# power_regulator_wii.net
KiCad netlist of a schematic drawn in EAGLE
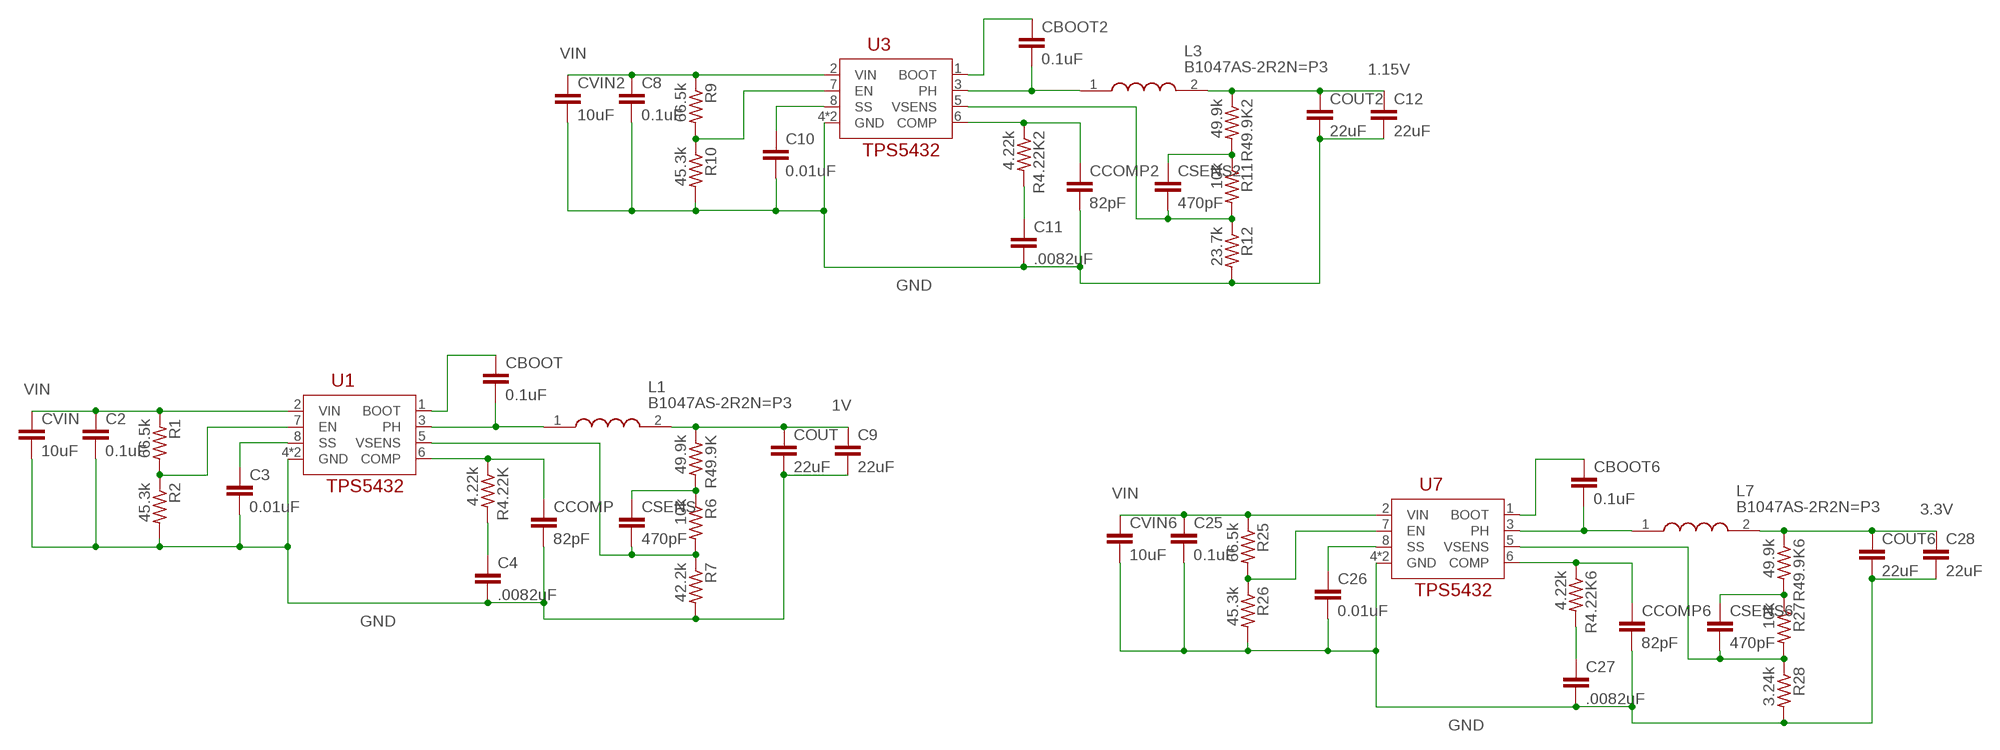
[diagram p0: schematic, sheet 1]

(export (version "E")
  (design (tool "Eeschema 10.0.6"))
  (components
    (comp (ref "C2")
      (value "0.1uF")
      (footprint "eagle-import:C0603")
      (libsource (lib "eagle-import") (part "C-EUC0603"))
    )
    (comp (ref "C3")
      (value "0.01uF")
      (footprint "eagle-import:C0603")
      (libsource (lib "eagle-import") (part "C-EUC0603"))
    )
    (comp (ref "C4")
      (value ".0082uF")
      (footprint "eagle-import:C0603")
      (libsource (lib "eagle-import") (part "C-EUC0603"))
    )
    (comp (ref "C8")
      (value "0.1uF")
      (footprint "eagle-import:C0603")
      (libsource (lib "eagle-import") (part "C-EUC0603"))
    )
    (comp (ref "C9")
      (value "22uF")
      (footprint "eagle-import:C0603")
      (libsource (lib "eagle-import") (part "C-EUC0603"))
    )
    (comp (ref "C10")
      (value "0.01uF")
      (footprint "eagle-import:C0603")
      (libsource (lib "eagle-import") (part "C-EUC0603"))
    )
    (comp (ref "C11")
      (value ".0082uF")
      (footprint "eagle-import:C0603")
      (libsource (lib "eagle-import") (part "C-EUC0603"))
    )
    (comp (ref "C12")
      (value "22uF")
      (footprint "eagle-import:C0603")
      (libsource (lib "eagle-import") (part "C-EUC0603"))
    )
    (comp (ref "C25")
      (value "0.1uF")
      (footprint "eagle-import:C0603")
      (libsource (lib "eagle-import") (part "C-EUC0603"))
    )
    (comp (ref "C26")
      (value "0.01uF")
      (footprint "eagle-import:C0603")
      (libsource (lib "eagle-import") (part "C-EUC0603"))
    )
    (comp (ref "C27")
      (value ".0082uF")
      (footprint "eagle-import:C0603")
      (libsource (lib "eagle-import") (part "C-EUC0603"))
    )
    (comp (ref "C28")
      (value "22uF")
      (footprint "eagle-import:C0603")
      (libsource (lib "eagle-import") (part "C-EUC0603"))
    )
    (comp (ref "CBOOT")
      (value "0.1uF")
      (footprint "eagle-import:C0603")
      (libsource (lib "eagle-import") (part "C-EUC0603"))
    )
    (comp (ref "CBOOT2")
      (value "0.1uF")
      (footprint "eagle-import:C0603")
      (libsource (lib "eagle-import") (part "C-EUC0603"))
    )
    (comp (ref "CBOOT6")
      (value "0.1uF")
      (footprint "eagle-import:C0603")
      (libsource (lib "eagle-import") (part "C-EUC0603"))
    )
    (comp (ref "CCOMP")
      (value "82pF")
      (footprint "eagle-import:C0603")
      (libsource (lib "eagle-import") (part "C-EUC0603"))
    )
    (comp (ref "CCOMP2")
      (value "82pF")
      (footprint "eagle-import:C0603")
      (libsource (lib "eagle-import") (part "C-EUC0603"))
    )
    (comp (ref "CCOMP6")
      (value "82pF")
      (footprint "eagle-import:C0603")
      (libsource (lib "eagle-import") (part "C-EUC0603"))
    )
    (comp (ref "COUT")
      (value "22uF")
      (footprint "eagle-import:C0603")
      (libsource (lib "eagle-import") (part "C-EUC0603"))
    )
    (comp (ref "COUT2")
      (value "22uF")
      (footprint "eagle-import:C0603")
      (libsource (lib "eagle-import") (part "C-EUC0603"))
    )
    (comp (ref "COUT6")
      (value "22uF")
      (footprint "eagle-import:C0603")
      (libsource (lib "eagle-import") (part "C-EUC0603"))
    )
    (comp (ref "CSENS")
      (value "470pF")
      (footprint "eagle-import:C0603")
      (libsource (lib "eagle-import") (part "C-EUC0603"))
    )
    (comp (ref "CSENS2")
      (value "470pF")
      (footprint "eagle-import:C0603")
      (libsource (lib "eagle-import") (part "C-EUC0603"))
    )
    (comp (ref "CSENS6")
      (value "470pF")
      (footprint "eagle-import:C0603")
      (libsource (lib "eagle-import") (part "C-EUC0603"))
    )
    (comp (ref "CVIN")
      (value "10uF")
      (footprint "eagle-import:C0603")
      (libsource (lib "eagle-import") (part "C-EUC0603"))
    )
    (comp (ref "CVIN2")
      (value "10uF")
      (footprint "eagle-import:C0603")
      (libsource (lib "eagle-import") (part "C-EUC0603"))
    )
    (comp (ref "CVIN6")
      (value "10uF")
      (footprint "eagle-import:C0603")
      (libsource (lib "eagle-import") (part "C-EUC0603"))
    )
    (comp (ref "L1")
      (value "B1047AS-2R2N=P3")
      (footprint "eagle-import:INDPM7474X500N")
      (libsource (lib "eagle-import") (part "B1047AS-2R2N=P3"))
    )
    (comp (ref "L3")
      (value "B1047AS-2R2N=P3")
      (footprint "eagle-import:INDPM7474X500N")
      (libsource (lib "eagle-import") (part "B1047AS-2R2N=P3"))
    )
    (comp (ref "L7")
      (value "B1047AS-2R2N=P3")
      (footprint "eagle-import:INDPM7474X500N")
      (libsource (lib "eagle-import") (part "B1047AS-2R2N=P3"))
    )
    (comp (ref "R1")
      (value "66.5k")
      (footprint "eagle-import:R0603")
      (libsource (lib "eagle-import") (part "R-US_R0603"))
    )
    (comp (ref "R2")
      (value "45.3k")
      (footprint "eagle-import:R0603")
      (libsource (lib "eagle-import") (part "R-US_R0603"))
    )
    (comp (ref "R4.22K")
      (value "4.22k")
      (footprint "eagle-import:R0603")
      (libsource (lib "eagle-import") (part "R-US_R0603"))
    )
    (comp (ref "R4.22K2")
      (value "4.22k")
      (footprint "eagle-import:R0603")
      (libsource (lib "eagle-import") (part "R-US_R0603"))
    )
    (comp (ref "R4.22K6")
      (value "4.22k")
      (footprint "eagle-import:R0603")
      (libsource (lib "eagle-import") (part "R-US_R0603"))
    )
    (comp (ref "R6")
      (value "10k")
      (footprint "eagle-import:R0603")
      (libsource (lib "eagle-import") (part "R-US_R0603"))
    )
    (comp (ref "R7")
      (value "42.2k")
      (footprint "eagle-import:R0603")
      (libsource (lib "eagle-import") (part "R-US_R0603"))
    )
    (comp (ref "R9")
      (value "66.5k")
      (footprint "eagle-import:R0603")
      (libsource (lib "eagle-import") (part "R-US_R0603"))
    )
    (comp (ref "R10")
      (value "45.3k")
      (footprint "eagle-import:R0603")
      (libsource (lib "eagle-import") (part "R-US_R0603"))
    )
    (comp (ref "R11")
      (value "10k")
      (footprint "eagle-import:R0603")
      (libsource (lib "eagle-import") (part "R-US_R0603"))
    )
    (comp (ref "R12")
      (value "23.7k")
      (footprint "eagle-import:R0603")
      (libsource (lib "eagle-import") (part "R-US_R0603"))
    )
    (comp (ref "R25")
      (value "66.5k")
      (footprint "eagle-import:R0603")
      (libsource (lib "eagle-import") (part "R-US_R0603"))
    )
    (comp (ref "R26")
      (value "45.3k")
      (footprint "eagle-import:R0603")
      (libsource (lib "eagle-import") (part "R-US_R0603"))
    )
    (comp (ref "R27")
      (value "10k")
      (footprint "eagle-import:R0603")
      (libsource (lib "eagle-import") (part "R-US_R0603"))
    )
    (comp (ref "R28")
      (value "3.24k")
      (footprint "eagle-import:R0603")
      (libsource (lib "eagle-import") (part "R-US_R0603"))
    )
    (comp (ref "R49.9K")
      (value "49.9k")
      (footprint "eagle-import:R0603")
      (libsource (lib "eagle-import") (part "R-US_R0603"))
    )
    (comp (ref "R49.9K2")
      (value "49.9k")
      (footprint "eagle-import:R0603")
      (libsource (lib "eagle-import") (part "R-US_R0603"))
    )
    (comp (ref "R49.9K6")
      (value "49.9k")
      (footprint "eagle-import:R0603")
      (libsource (lib "eagle-import") (part "R-US_R0603"))
    )
    (comp (ref "U1")
      (value "TPS5432")
      (footprint "eagle-import:SO-8")
      (libsource (lib "eagle-import") (part "TPS5432"))
    )
    (comp (ref "U3")
      (value "TPS5432")
      (footprint "eagle-import:SO-8")
      (libsource (lib "eagle-import") (part "TPS5432"))
    )
    (comp (ref "U7")
      (value "TPS5432")
      (footprint "eagle-import:SO-8")
      (libsource (lib "eagle-import") (part "TPS5432"))
    )
  )
  (nets
    (net (code "1") (name "/1.15V") (class "Default")
      (node (ref "C12") (pin "1") (pinfunction "1_1") (pintype "passive"))
      (node (ref "COUT2") (pin "1") (pinfunction "1_1") (pintype "passive"))
      (node (ref "L3") (pin "2") (pinfunction "2_2") (pintype "bidirectional"))
      (node (ref "R49.9K2") (pin "1") (pinfunction "1_1") (pintype "passive"))
    )
    (net (code "2") (name "/1V") (class "Default")
      (node (ref "C9") (pin "1") (pinfunction "1_1") (pintype "passive"))
      (node (ref "COUT") (pin "1") (pinfunction "1_1") (pintype "passive"))
      (node (ref "L1") (pin "2") (pinfunction "2_2") (pintype "bidirectional"))
      (node (ref "R49.9K") (pin "1") (pinfunction "1_1") (pintype "passive"))
    )
    (net (code "3") (name "/3.3V") (class "Default")
      (node (ref "C28") (pin "1") (pinfunction "1_1") (pintype "passive"))
      (node (ref "COUT6") (pin "1") (pinfunction "1_1") (pintype "passive"))
      (node (ref "L7") (pin "2") (pinfunction "2_2") (pintype "bidirectional"))
      (node (ref "R49.9K6") (pin "1") (pinfunction "1_1") (pintype "passive"))
    )
    (net (code "4") (name "/GND") (class "Default")
      (node (ref "C10") (pin "2") (pinfunction "2_2") (pintype "passive"))
      (node (ref "C11") (pin "2") (pinfunction "2_2") (pintype "passive"))
      (node (ref "C12") (pin "2") (pinfunction "2_2") (pintype "passive"))
      (node (ref "C2") (pin "2") (pinfunction "2_2") (pintype "passive"))
      (node (ref "C25") (pin "2") (pinfunction "2_2") (pintype "passive"))
      (node (ref "C26") (pin "2") (pinfunction "2_2") (pintype "passive"))
      (node (ref "C27") (pin "2") (pinfunction "2_2") (pintype "passive"))
      (node (ref "C28") (pin "2") (pinfunction "2_2") (pintype "passive"))
      (node (ref "C3") (pin "2") (pinfunction "2_2") (pintype "passive"))
      (node (ref "C4") (pin "2") (pinfunction "2_2") (pintype "passive"))
      (node (ref "C8") (pin "2") (pinfunction "2_2") (pintype "passive"))
      (node (ref "C9") (pin "2") (pinfunction "2_2") (pintype "passive"))
      (node (ref "CCOMP") (pin "2") (pinfunction "2_2") (pintype "passive"))
      (node (ref "CCOMP2") (pin "2") (pinfunction "2_2") (pintype "passive"))
      (node (ref "CCOMP6") (pin "2") (pinfunction "2_2") (pintype "passive"))
      (node (ref "COUT") (pin "2") (pinfunction "2_2") (pintype "passive"))
      (node (ref "COUT2") (pin "2") (pinfunction "2_2") (pintype "passive"))
      (node (ref "COUT6") (pin "2") (pinfunction "2_2") (pintype "passive"))
      (node (ref "CVIN") (pin "2") (pinfunction "2_2") (pintype "passive"))
      (node (ref "CVIN2") (pin "2") (pinfunction "2_2") (pintype "passive"))
      (node (ref "CVIN6") (pin "2") (pinfunction "2_2") (pintype "passive"))
      (node (ref "R10") (pin "2") (pinfunction "2_2") (pintype "passive"))
      (node (ref "R12") (pin "2") (pinfunction "2_2") (pintype "passive"))
      (node (ref "R2") (pin "2") (pinfunction "2_2") (pintype "passive"))
      (node (ref "R26") (pin "2") (pinfunction "2_2") (pintype "passive"))
      (node (ref "R28") (pin "2") (pinfunction "2_2") (pintype "passive"))
      (node (ref "R7") (pin "2") (pinfunction "2_2") (pintype "passive"))
      (node (ref "U1") (pin "4") (pinfunction "GND_4") (pintype "passive"))
      (node (ref "U1") (pin "PAD") (pinfunction "GND_PAD") (pintype "passive"))
      (node (ref "U3") (pin "4") (pinfunction "GND_4") (pintype "passive"))
      (node (ref "U3") (pin "PAD") (pinfunction "GND_PAD") (pintype "passive"))
      (node (ref "U7") (pin "4") (pinfunction "GND_4") (pintype "passive"))
      (node (ref "U7") (pin "PAD") (pinfunction "GND_PAD") (pintype "passive"))
    )
    (net (code "5") (name "/VIN") (class "Default")
      (node (ref "C2") (pin "1") (pinfunction "1_1") (pintype "passive"))
      (node (ref "C25") (pin "1") (pinfunction "1_1") (pintype "passive"))
      (node (ref "C8") (pin "1") (pinfunction "1_1") (pintype "passive"))
      (node (ref "CVIN") (pin "1") (pinfunction "1_1") (pintype "passive"))
      (node (ref "CVIN2") (pin "1") (pinfunction "1_1") (pintype "passive"))
      (node (ref "CVIN6") (pin "1") (pinfunction "1_1") (pintype "passive"))
      (node (ref "R1") (pin "1") (pinfunction "1_1") (pintype "passive"))
      (node (ref "R25") (pin "1") (pinfunction "1_1") (pintype "passive"))
      (node (ref "R9") (pin "1") (pinfunction "1_1") (pintype "passive"))
      (node (ref "U1") (pin "2") (pinfunction "VIN_2") (pintype "passive"))
      (node (ref "U3") (pin "2") (pinfunction "VIN_2") (pintype "passive"))
      (node (ref "U7") (pin "2") (pinfunction "VIN_2") (pintype "passive"))
    )
    (net (code "6") (name "Net-(C4-Pad1)") (class "Default")
      (node (ref "C4") (pin "1") (pinfunction "1_1") (pintype "passive"))
      (node (ref "R4.22K") (pin "2") (pinfunction "2_2") (pintype "passive"))
    )
    (net (code "7") (name "Net-(C11-Pad1)") (class "Default")
      (node (ref "C11") (pin "1") (pinfunction "1_1") (pintype "passive"))
      (node (ref "R4.22K2") (pin "2") (pinfunction "2_2") (pintype "passive"))
    )
    (net (code "8") (name "Net-(C27-Pad1)") (class "Default")
      (node (ref "C27") (pin "1") (pinfunction "1_1") (pintype "passive"))
      (node (ref "R4.22K6") (pin "2") (pinfunction "2_2") (pintype "passive"))
    )
    (net (code "9") (name "Net-(CSENS-Pad1)") (class "Default")
      (node (ref "CSENS") (pin "1") (pinfunction "1_1") (pintype "passive"))
      (node (ref "R49.9K") (pin "2") (pinfunction "2_2") (pintype "passive"))
      (node (ref "R6") (pin "1") (pinfunction "1_1") (pintype "passive"))
    )
    (net (code "10") (name "Net-(CSENS2-Pad1)") (class "Default")
      (node (ref "CSENS2") (pin "1") (pinfunction "1_1") (pintype "passive"))
      (node (ref "R11") (pin "1") (pinfunction "1_1") (pintype "passive"))
      (node (ref "R49.9K2") (pin "2") (pinfunction "2_2") (pintype "passive"))
    )
    (net (code "11") (name "Net-(CSENS6-Pad1)") (class "Default")
      (node (ref "CSENS6") (pin "1") (pinfunction "1_1") (pintype "passive"))
      (node (ref "R27") (pin "1") (pinfunction "1_1") (pintype "passive"))
      (node (ref "R49.9K6") (pin "2") (pinfunction "2_2") (pintype "passive"))
    )
    (net (code "12") (name "Net-(U1-BOOT)") (class "Default")
      (node (ref "CBOOT") (pin "1") (pinfunction "1_1") (pintype "passive"))
      (node (ref "U1") (pin "1") (pinfunction "BOOT_1") (pintype "passive"))
    )
    (net (code "13") (name "Net-(U1-COMP)") (class "Default")
      (node (ref "CCOMP") (pin "1") (pinfunction "1_1") (pintype "passive"))
      (node (ref "R4.22K") (pin "1") (pinfunction "1_1") (pintype "passive"))
      (node (ref "U1") (pin "6") (pinfunction "COMP_6") (pintype "passive"))
    )
    (net (code "14") (name "Net-(U1-EN)") (class "Default")
      (node (ref "R1") (pin "2") (pinfunction "2_2") (pintype "passive"))
      (node (ref "R2") (pin "1") (pinfunction "1_1") (pintype "passive"))
      (node (ref "U1") (pin "7") (pinfunction "EN_7") (pintype "passive"))
    )
    (net (code "15") (name "Net-(U1-PH)") (class "Default")
      (node (ref "CBOOT") (pin "2") (pinfunction "2_2") (pintype "passive"))
      (node (ref "L1") (pin "1") (pinfunction "1_1") (pintype "bidirectional"))
      (node (ref "U1") (pin "3") (pinfunction "PH_3") (pintype "passive"))
    )
    (net (code "16") (name "Net-(U1-SS)") (class "Default")
      (node (ref "C3") (pin "1") (pinfunction "1_1") (pintype "passive"))
      (node (ref "U1") (pin "8") (pinfunction "SS_8") (pintype "passive"))
    )
    (net (code "17") (name "Net-(U1-VSENS)") (class "Default")
      (node (ref "CSENS") (pin "2") (pinfunction "2_2") (pintype "passive"))
      (node (ref "R6") (pin "2") (pinfunction "2_2") (pintype "passive"))
      (node (ref "R7") (pin "1") (pinfunction "1_1") (pintype "passive"))
      (node (ref "U1") (pin "5") (pinfunction "VSENS_5") (pintype "passive"))
    )
    (net (code "18") (name "Net-(U3-BOOT)") (class "Default")
      (node (ref "CBOOT2") (pin "1") (pinfunction "1_1") (pintype "passive"))
      (node (ref "U3") (pin "1") (pinfunction "BOOT_1") (pintype "passive"))
    )
    (net (code "19") (name "Net-(U3-COMP)") (class "Default")
      (node (ref "CCOMP2") (pin "1") (pinfunction "1_1") (pintype "passive"))
      (node (ref "R4.22K2") (pin "1") (pinfunction "1_1") (pintype "passive"))
      (node (ref "U3") (pin "6") (pinfunction "COMP_6") (pintype "passive"))
    )
    (net (code "20") (name "Net-(U3-EN)") (class "Default")
      (node (ref "R10") (pin "1") (pinfunction "1_1") (pintype "passive"))
      (node (ref "R9") (pin "2") (pinfunction "2_2") (pintype "passive"))
      (node (ref "U3") (pin "7") (pinfunction "EN_7") (pintype "passive"))
    )
    (net (code "21") (name "Net-(U3-PH)") (class "Default")
      (node (ref "CBOOT2") (pin "2") (pinfunction "2_2") (pintype "passive"))
      (node (ref "L3") (pin "1") (pinfunction "1_1") (pintype "bidirectional"))
      (node (ref "U3") (pin "3") (pinfunction "PH_3") (pintype "passive"))
    )
    (net (code "22") (name "Net-(U3-SS)") (class "Default")
      (node (ref "C10") (pin "1") (pinfunction "1_1") (pintype "passive"))
      (node (ref "U3") (pin "8") (pinfunction "SS_8") (pintype "passive"))
    )
    (net (code "23") (name "Net-(U3-VSENS)") (class "Default")
      (node (ref "CSENS2") (pin "2") (pinfunction "2_2") (pintype "passive"))
      (node (ref "R11") (pin "2") (pinfunction "2_2") (pintype "passive"))
      (node (ref "R12") (pin "1") (pinfunction "1_1") (pintype "passive"))
      (node (ref "U3") (pin "5") (pinfunction "VSENS_5") (pintype "passive"))
    )
    (net (code "24") (name "Net-(U7-BOOT)") (class "Default")
      (node (ref "CBOOT6") (pin "1") (pinfunction "1_1") (pintype "passive"))
      (node (ref "U7") (pin "1") (pinfunction "BOOT_1") (pintype "passive"))
    )
    (net (code "25") (name "Net-(U7-COMP)") (class "Default")
      (node (ref "CCOMP6") (pin "1") (pinfunction "1_1") (pintype "passive"))
      (node (ref "R4.22K6") (pin "1") (pinfunction "1_1") (pintype "passive"))
      (node (ref "U7") (pin "6") (pinfunction "COMP_6") (pintype "passive"))
    )
    (net (code "26") (name "Net-(U7-EN)") (class "Default")
      (node (ref "R25") (pin "2") (pinfunction "2_2") (pintype "passive"))
      (node (ref "R26") (pin "1") (pinfunction "1_1") (pintype "passive"))
      (node (ref "U7") (pin "7") (pinfunction "EN_7") (pintype "passive"))
    )
    (net (code "27") (name "Net-(U7-PH)") (class "Default")
      (node (ref "CBOOT6") (pin "2") (pinfunction "2_2") (pintype "passive"))
      (node (ref "L7") (pin "1") (pinfunction "1_1") (pintype "bidirectional"))
      (node (ref "U7") (pin "3") (pinfunction "PH_3") (pintype "passive"))
    )
    (net (code "28") (name "Net-(U7-SS)") (class "Default")
      (node (ref "C26") (pin "1") (pinfunction "1_1") (pintype "passive"))
      (node (ref "U7") (pin "8") (pinfunction "SS_8") (pintype "passive"))
    )
    (net (code "29") (name "Net-(U7-VSENS)") (class "Default")
      (node (ref "CSENS6") (pin "2") (pinfunction "2_2") (pintype "passive"))
      (node (ref "R27") (pin "2") (pinfunction "2_2") (pintype "passive"))
      (node (ref "R28") (pin "1") (pinfunction "1_1") (pintype "passive"))
      (node (ref "U7") (pin "5") (pinfunction "VSENS_5") (pintype "passive"))
    )
  )
)
